# ControlInputs.net
KiCad netlist of a schematic drawn in EAGLE
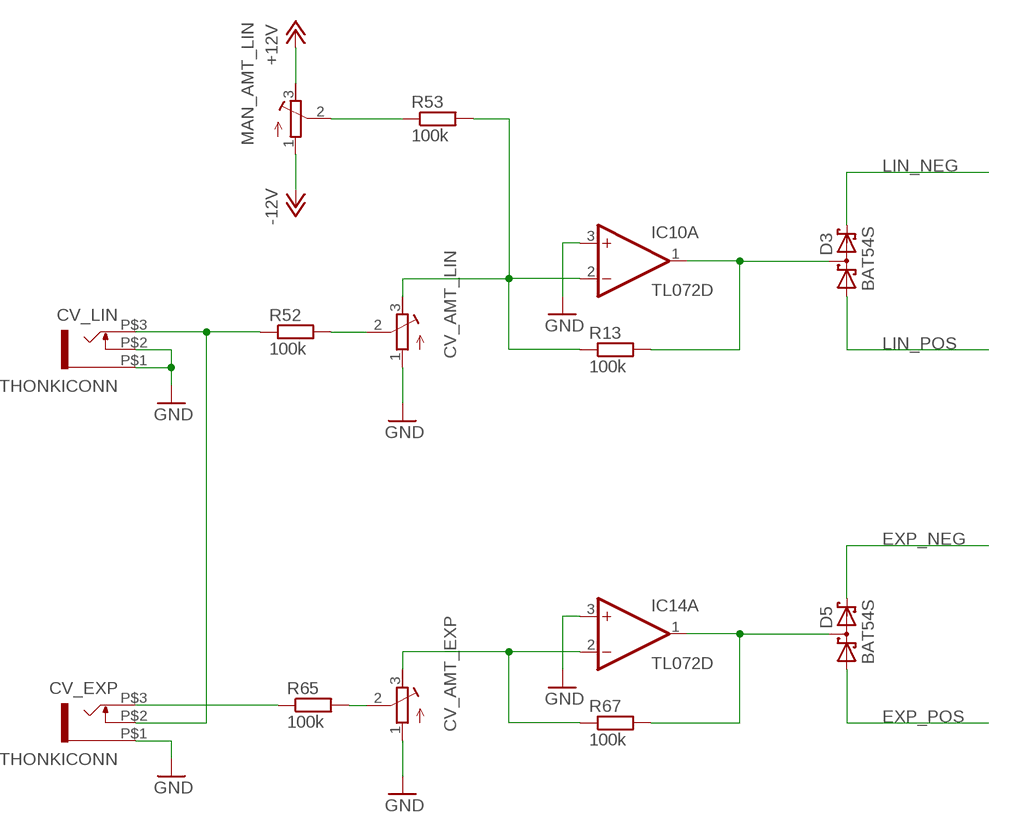
[diagram p0: schematic, sheet 1]

(export (version "E")
  (design (tool "Eeschema 10.0.6"))
  (components
    (comp (ref "CV_AMT_EXP")
      (value "R-TRIMM64X")
      (footprint "eagle-import:RTRIM64X")
      (libsource (lib "eagle-import") (part "R-TRIMM64X"))
    )
    (comp (ref "CV_AMT_LIN")
      (value "R-TRIMM64X")
      (footprint "eagle-import:RTRIM64X")
      (libsource (lib "eagle-import") (part "R-TRIMM64X"))
    )
    (comp (ref "CV_EXP")
      (value "THONKICONN")
      (footprint "eagle-import:THONKICONN")
      (libsource (lib "eagle-import") (part "THONKICONN"))
    )
    (comp (ref "CV_LIN")
      (value "THONKICONN")
      (footprint "eagle-import:THONKICONN")
      (libsource (lib "eagle-import") (part "THONKICONN"))
    )
    (comp (ref "D3")
      (value "BAT54S")
      (footprint "eagle-import:SOT23")
      (libsource (lib "eagle-import") (part "BAT54S"))
    )
    (comp (ref "D5")
      (value "BAT54S")
      (footprint "eagle-import:SOT23")
      (libsource (lib "eagle-import") (part "BAT54S"))
    )
    (comp (ref "IC10")
      (value "TL072D")
      (footprint "eagle-import:SO08")
      (libsource (lib "eagle-import") (part "TL072D"))
    )
    (comp (ref "IC14")
      (value "TL072D")
      (footprint "eagle-import:SO08")
      (libsource (lib "eagle-import") (part "TL072D"))
    )
    (comp (ref "MAN_AMT_LIN")
      (value "R-TRIMM64X")
      (footprint "eagle-import:RTRIM64X")
      (libsource (lib "eagle-import") (part "R-TRIMM64X"))
    )
    (comp (ref "R13")
      (value "100k")
      (footprint "eagle-import:0603")
      (libsource (lib "eagle-import") (part "R-EU_0603"))
    )
    (comp (ref "R52")
      (value "100k")
      (footprint "eagle-import:0603")
      (libsource (lib "eagle-import") (part "R-EU_0603"))
    )
    (comp (ref "R53")
      (value "100k")
      (footprint "eagle-import:0603")
      (libsource (lib "eagle-import") (part "R-EU_0603"))
    )
    (comp (ref "R65")
      (value "100k")
      (footprint "eagle-import:0603")
      (libsource (lib "eagle-import") (part "R-EU_0603"))
    )
    (comp (ref "R67")
      (value "100k")
      (footprint "eagle-import:0603")
      (libsource (lib "eagle-import") (part "R-EU_0603"))
    )
  )
  (nets
    (net (code "1") (name "+12V") (class "Default")
      (node (ref "MAN_AMT_LIN") (pin "3") (pinfunction "E_3") (pintype "passive"))
    )
    (net (code "2") (name "-12V") (class "Default")
      (node (ref "MAN_AMT_LIN") (pin "1") (pinfunction "A_1") (pintype "passive"))
    )
    (net (code "3") (name "/EXP_NEG") (class "Default")
      (node (ref "D5") (pin "2") (pinfunction "C2_2") (pintype "passive"))
    )
    (net (code "4") (name "/EXP_POS") (class "Default")
      (node (ref "D5") (pin "1") (pinfunction "A1_1") (pintype "passive"))
    )
    (net (code "5") (name "/LIN_NEG") (class "Default")
      (node (ref "D3") (pin "2") (pinfunction "C2_2") (pintype "passive"))
    )
    (net (code "6") (name "/LIN_POS") (class "Default")
      (node (ref "D3") (pin "1") (pinfunction "A1_1") (pintype "passive"))
    )
    (net (code "7") (name "GND") (class "Default")
      (node (ref "CV_AMT_EXP") (pin "1") (pinfunction "A_1") (pintype "passive"))
      (node (ref "CV_AMT_LIN") (pin "1") (pinfunction "A_1") (pintype "passive"))
      (node (ref "CV_EXP") (pin "P$1") (pinfunction "5_P$1") (pintype "passive"))
      (node (ref "CV_LIN") (pin "P$1") (pinfunction "5_P$1") (pintype "passive"))
      (node (ref "CV_LIN") (pin "P$2") (pinfunction "4_P$2") (pintype "passive"))
      (node (ref "IC10") (pin "3") (pinfunction "+IN_3") (pintype "input"))
      (node (ref "IC14") (pin "3") (pinfunction "+IN_3") (pintype "input"))
    )
    (net (code "8") (name "Net-(CV_AMT_EXP-E)") (class "Default")
      (node (ref "CV_AMT_EXP") (pin "3") (pinfunction "E_3") (pintype "passive"))
      (node (ref "IC14") (pin "2") (pinfunction "-IN_2") (pintype "input"))
      (node (ref "R67") (pin "1") (pinfunction "1_1") (pintype "passive"))
    )
    (net (code "9") (name "Net-(CV_AMT_EXP-S)") (class "Default")
      (node (ref "CV_AMT_EXP") (pin "2") (pinfunction "S_2") (pintype "passive"))
      (node (ref "R65") (pin "2") (pinfunction "2_2") (pintype "passive"))
    )
    (net (code "10") (name "Net-(CV_AMT_LIN-E)") (class "Default")
      (node (ref "CV_AMT_LIN") (pin "3") (pinfunction "E_3") (pintype "passive"))
      (node (ref "IC10") (pin "2") (pinfunction "-IN_2") (pintype "input"))
      (node (ref "R13") (pin "1") (pinfunction "1_1") (pintype "passive"))
      (node (ref "R53") (pin "2") (pinfunction "2_2") (pintype "passive"))
    )
    (net (code "11") (name "Net-(CV_AMT_LIN-S)") (class "Default")
      (node (ref "CV_AMT_LIN") (pin "2") (pinfunction "S_2") (pintype "passive"))
      (node (ref "R52") (pin "2") (pinfunction "2_2") (pintype "passive"))
    )
    (net (code "12") (name "Net-(CV_EXP-3)") (class "Default")
      (node (ref "CV_EXP") (pin "P$3") (pinfunction "3_P$3") (pintype "passive"))
      (node (ref "R65") (pin "1") (pinfunction "1_1") (pintype "passive"))
    )
    (net (code "13") (name "Net-(CV_EXP-4)") (class "Default")
      (node (ref "CV_EXP") (pin "P$2") (pinfunction "4_P$2") (pintype "passive"))
      (node (ref "CV_LIN") (pin "P$3") (pinfunction "3_P$3") (pintype "passive"))
      (node (ref "R52") (pin "1") (pinfunction "1_1") (pintype "passive"))
    )
    (net (code "14") (name "Net-(D3-C1A2)") (class "Default")
      (node (ref "D3") (pin "3") (pinfunction "C1A2_3") (pintype "passive"))
      (node (ref "IC10") (pin "1") (pinfunction "OUT_1") (pintype "output"))
      (node (ref "R13") (pin "2") (pinfunction "2_2") (pintype "passive"))
    )
    (net (code "15") (name "Net-(D5-C1A2)") (class "Default")
      (node (ref "D5") (pin "3") (pinfunction "C1A2_3") (pintype "passive"))
      (node (ref "IC14") (pin "1") (pinfunction "OUT_1") (pintype "output"))
      (node (ref "R67") (pin "2") (pinfunction "2_2") (pintype "passive"))
    )
    (net (code "16") (name "Net-(MAN_AMT_LIN-S)") (class "Default")
      (node (ref "MAN_AMT_LIN") (pin "2") (pinfunction "S_2") (pintype "passive"))
      (node (ref "R53") (pin "1") (pinfunction "1_1") (pintype "passive"))
    )
  )
)
